# i2cLCD.net
KiCad netlist of a schematic drawn in EAGLE
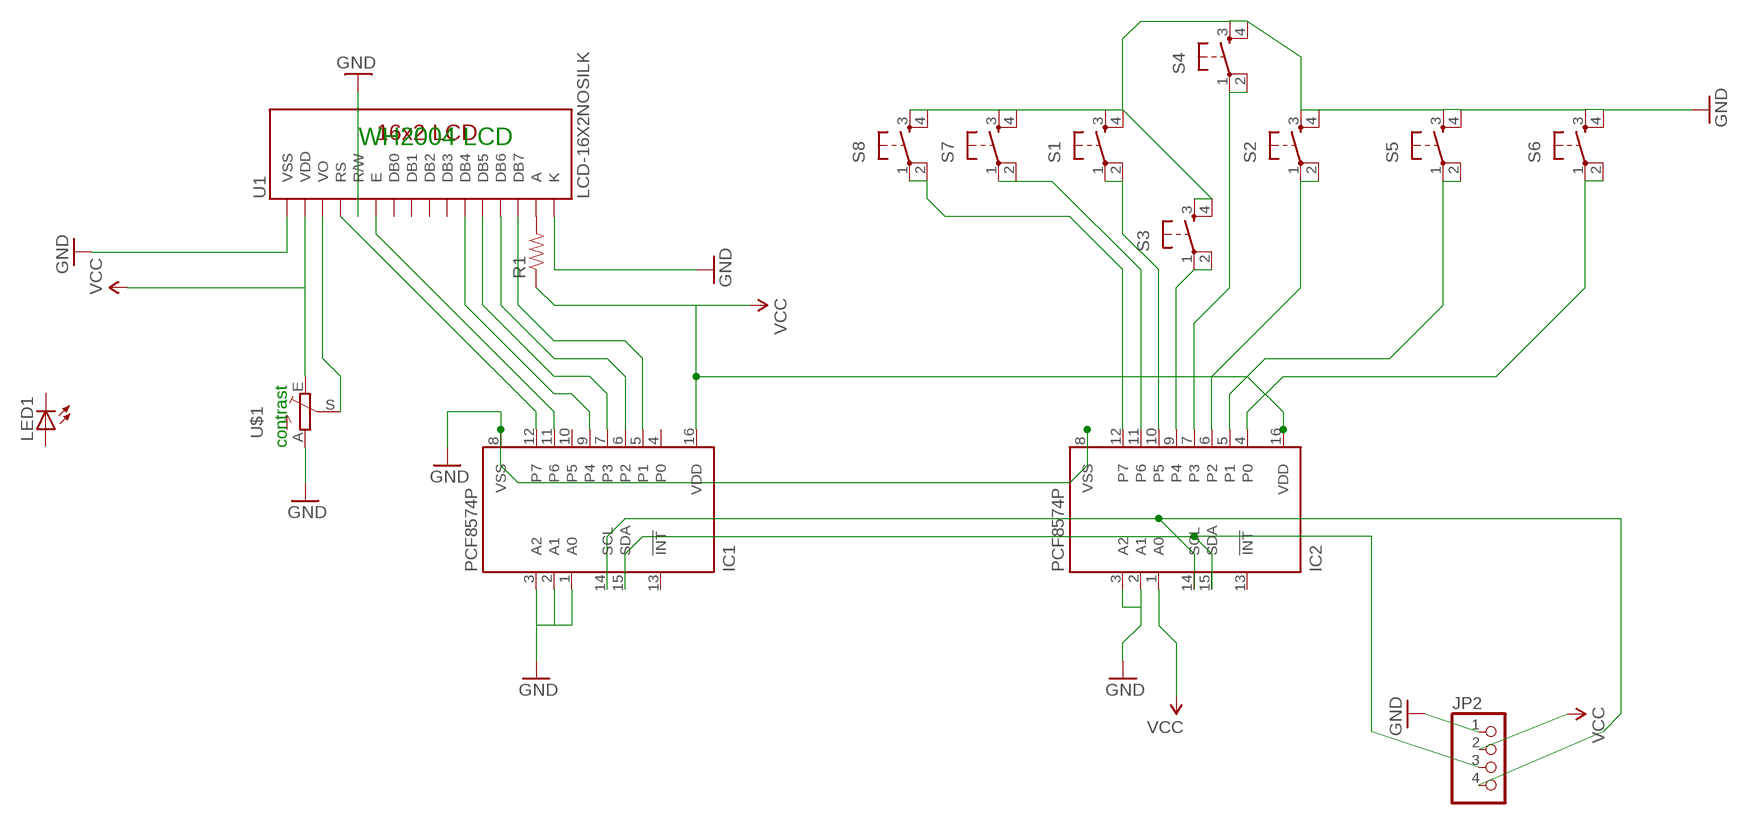
[diagram p0: schematic, sheet 1]

(export (version "E")
  (design (tool "Eeschema 10.0.6"))
  (components
    (comp (ref "IC1")
      (value "PCF8574P")
      (footprint "eagle-import:DIL16")
      (fields (field (name "MPN") "PCF8574PN"))
      (libsource (lib "eagle-import") (part "PCF8574P"))
    )
    (comp (ref "IC2")
      (value "PCF8574P")
      (footprint "eagle-import:DIL16")
      (fields
        (field (name "MPN") "PCF8574PN")
        (field (name "MPN_1") "PCF8574PN")
        (field (name "OC_FARNELL") "204020")
        (field (name "OC_NEWARK") "11N8515")
      )
      (libsource (lib "eagle-import") (part "PCF8574P"))
    )
    (comp (ref "JP2")
      (value "PINHD-1X4/90")
      (footprint "eagle-import:1X04_90")
      (libsource (lib "eagle-import") (part "PINHD-1X4/90"))
    )
    (comp (ref "LED1")
      (value "LED1206")
      (footprint "eagle-import:LED-1206")
      (libsource (lib "eagle-import") (part "LED1206"))
    )
    (comp (ref "R1")
      (value "RESISTORPTH-1/4W")
      (footprint "eagle-import:AXIAL-0.4")
      (libsource (lib "eagle-import") (part "RESISTORPTH-1/4W"))
    )
    (comp (ref "S1")
      (value "TAC_SWITCHPTH")
      (footprint "eagle-import:TACTILE-PTH")
      (libsource (lib "eagle-import") (part "TAC_SWITCHPTH"))
    )
    (comp (ref "S2")
      (value "TAC_SWITCHPTH")
      (footprint "eagle-import:TACTILE-PTH")
      (libsource (lib "eagle-import") (part "TAC_SWITCHPTH"))
    )
    (comp (ref "S3")
      (value "TAC_SWITCHPTH")
      (footprint "eagle-import:TACTILE-PTH")
      (libsource (lib "eagle-import") (part "TAC_SWITCHPTH"))
    )
    (comp (ref "S4")
      (value "TAC_SWITCHPTH")
      (footprint "eagle-import:TACTILE-PTH")
      (libsource (lib "eagle-import") (part "TAC_SWITCHPTH"))
    )
    (comp (ref "S5")
      (value "TAC_SWITCHPTH")
      (footprint "eagle-import:TACTILE-PTH")
      (libsource (lib "eagle-import") (part "TAC_SWITCHPTH"))
    )
    (comp (ref "S6")
      (value "TAC_SWITCHPTH")
      (footprint "eagle-import:TACTILE-PTH")
      (libsource (lib "eagle-import") (part "TAC_SWITCHPTH"))
    )
    (comp (ref "S7")
      (value "TAC_SWITCHPTH")
      (footprint "eagle-import:TACTILE-PTH")
      (libsource (lib "eagle-import") (part "TAC_SWITCHPTH"))
    )
    (comp (ref "S8")
      (value "TAC_SWITCHPTH")
      (footprint "eagle-import:TACTILE-PTH")
      (libsource (lib "eagle-import") (part "TAC_SWITCHPTH"))
    )
    (comp (ref "U$1")
      (value "TRIM_EU-CA9V")
      (footprint "eagle-import:CA9V")
      (libsource (lib "eagle-import") (part "TRIM_EU-CA9V"))
    )
    (comp (ref "U1")
      (value "LCD-16X2NOSILK")
      (footprint "eagle-import:LCD-16X2_NOSILK")
      (libsource (lib "eagle-import") (part "LCD-16X2NOSILK"))
    )
  )
  (nets
    (net (code "1") (name "GND") (class "Default")
      (node (ref "IC1") (pin "1") (pinfunction "A0_1") (pintype "input"))
      (node (ref "IC1") (pin "2") (pinfunction "A1_2") (pintype "input"))
      (node (ref "IC1") (pin "3") (pinfunction "A2_3") (pintype "input"))
      (node (ref "IC1") (pin "8") (pinfunction "VSS_8") (pintype "power_in"))
      (node (ref "IC2") (pin "2") (pinfunction "A1_2") (pintype "input"))
      (node (ref "IC2") (pin "3") (pinfunction "A2_3") (pintype "input"))
      (node (ref "IC2") (pin "8") (pinfunction "VSS_8") (pintype "power_in"))
      (node (ref "JP2") (pin "1") (pinfunction "1_1") (pintype "passive"))
      (node (ref "S1") (pin "3") (pinfunction "3_3") (pintype "passive"))
      (node (ref "S1") (pin "4") (pinfunction "4_4") (pintype "passive"))
      (node (ref "S2") (pin "3") (pinfunction "3_3") (pintype "passive"))
      (node (ref "S2") (pin "4") (pinfunction "4_4") (pintype "passive"))
      (node (ref "S3") (pin "3") (pinfunction "3_3") (pintype "passive"))
      (node (ref "S3") (pin "4") (pinfunction "4_4") (pintype "passive"))
      (node (ref "S4") (pin "3") (pinfunction "3_3") (pintype "passive"))
      (node (ref "S4") (pin "4") (pinfunction "4_4") (pintype "passive"))
      (node (ref "S5") (pin "3") (pinfunction "3_3") (pintype "passive"))
      (node (ref "S5") (pin "4") (pinfunction "4_4") (pintype "passive"))
      (node (ref "S6") (pin "3") (pinfunction "3_3") (pintype "passive"))
      (node (ref "S6") (pin "4") (pinfunction "4_4") (pintype "passive"))
      (node (ref "S7") (pin "3") (pinfunction "3_3") (pintype "passive"))
      (node (ref "S7") (pin "4") (pinfunction "4_4") (pintype "passive"))
      (node (ref "S8") (pin "3") (pinfunction "3_3") (pintype "passive"))
      (node (ref "S8") (pin "4") (pinfunction "4_4") (pintype "passive"))
      (node (ref "U$1") (pin "A") (pinfunction "A_A") (pintype "passive"))
      (node (ref "U1") (pin "1") (pinfunction "VSS_1") (pintype "power_in"))
      (node (ref "U1") (pin "16") (pinfunction "K_16") (pintype "power_in"))
      (node (ref "U1") (pin "5") (pinfunction "R/W_5") (pintype "input"))
    )
    (net (code "2") (name "Net-(IC1-P1)") (class "Default")
      (node (ref "IC1") (pin "5") (pinfunction "P1_5") (pintype "bidirectional"))
      (node (ref "U1") (pin "14") (pinfunction "DB7_14") (pintype "bidirectional"))
    )
    (net (code "3") (name "Net-(IC1-P2)") (class "Default")
      (node (ref "IC1") (pin "6") (pinfunction "P2_6") (pintype "bidirectional"))
      (node (ref "U1") (pin "13") (pinfunction "DB6_13") (pintype "bidirectional"))
    )
    (net (code "4") (name "Net-(IC1-P3)") (class "Default")
      (node (ref "IC1") (pin "7") (pinfunction "P3_7") (pintype "bidirectional"))
      (node (ref "U1") (pin "12") (pinfunction "DB5_12") (pintype "bidirectional"))
    )
    (net (code "5") (name "Net-(IC1-P4)") (class "Default")
      (node (ref "IC1") (pin "9") (pinfunction "P4_9") (pintype "bidirectional"))
      (node (ref "U1") (pin "11") (pinfunction "DB4_11") (pintype "bidirectional"))
    )
    (net (code "6") (name "Net-(IC1-P6)") (class "Default")
      (node (ref "IC1") (pin "11") (pinfunction "P6_11") (pintype "bidirectional"))
      (node (ref "U1") (pin "6") (pinfunction "E_6") (pintype "input"))
    )
    (net (code "7") (name "Net-(IC1-P7)") (class "Default")
      (node (ref "IC1") (pin "12") (pinfunction "P7_12") (pintype "bidirectional"))
      (node (ref "U1") (pin "4") (pinfunction "RS_4") (pintype "input"))
    )
    (net (code "8") (name "Net-(IC1-SCL)") (class "Default")
      (node (ref "IC1") (pin "14") (pinfunction "SCL_14") (pintype "input"))
      (node (ref "IC2") (pin "14") (pinfunction "SCL_14") (pintype "input"))
      (node (ref "JP2") (pin "4") (pinfunction "4_4") (pintype "passive"))
    )
    (net (code "9") (name "Net-(IC1-SDA)") (class "Default")
      (node (ref "IC1") (pin "15") (pinfunction "SDA_15") (pintype "bidirectional"))
      (node (ref "IC2") (pin "15") (pinfunction "SDA_15") (pintype "bidirectional"))
      (node (ref "JP2") (pin "3") (pinfunction "3_3") (pintype "passive"))
    )
    (net (code "10") (name "Net-(IC2-P0)") (class "Default")
      (node (ref "IC2") (pin "4") (pinfunction "P0_4") (pintype "bidirectional"))
      (node (ref "S6") (pin "1") (pinfunction "1_1") (pintype "passive"))
      (node (ref "S6") (pin "2") (pinfunction "2_2") (pintype "passive"))
    )
    (net (code "11") (name "Net-(IC2-P1)") (class "Default")
      (node (ref "IC2") (pin "5") (pinfunction "P1_5") (pintype "bidirectional"))
      (node (ref "S5") (pin "1") (pinfunction "1_1") (pintype "passive"))
      (node (ref "S5") (pin "2") (pinfunction "2_2") (pintype "passive"))
    )
    (net (code "12") (name "Net-(IC2-P2)") (class "Default")
      (node (ref "IC2") (pin "6") (pinfunction "P2_6") (pintype "bidirectional"))
      (node (ref "S2") (pin "1") (pinfunction "1_1") (pintype "passive"))
      (node (ref "S2") (pin "2") (pinfunction "2_2") (pintype "passive"))
    )
    (net (code "13") (name "Net-(IC2-P3)") (class "Default")
      (node (ref "IC2") (pin "7") (pinfunction "P3_7") (pintype "bidirectional"))
      (node (ref "S4") (pin "1") (pinfunction "1_1") (pintype "passive"))
      (node (ref "S4") (pin "2") (pinfunction "2_2") (pintype "passive"))
    )
    (net (code "14") (name "Net-(IC2-P4)") (class "Default")
      (node (ref "IC2") (pin "9") (pinfunction "P4_9") (pintype "bidirectional"))
      (node (ref "S3") (pin "1") (pinfunction "1_1") (pintype "passive"))
      (node (ref "S3") (pin "2") (pinfunction "2_2") (pintype "passive"))
    )
    (net (code "15") (name "Net-(IC2-P5)") (class "Default")
      (node (ref "IC2") (pin "10") (pinfunction "P5_10") (pintype "bidirectional"))
      (node (ref "S1") (pin "1") (pinfunction "1_1") (pintype "passive"))
      (node (ref "S1") (pin "2") (pinfunction "2_2") (pintype "passive"))
    )
    (net (code "16") (name "Net-(IC2-P6)") (class "Default")
      (node (ref "IC2") (pin "11") (pinfunction "P6_11") (pintype "bidirectional"))
      (node (ref "S7") (pin "1") (pinfunction "1_1") (pintype "passive"))
      (node (ref "S7") (pin "2") (pinfunction "2_2") (pintype "passive"))
    )
    (net (code "17") (name "Net-(IC2-P7)") (class "Default")
      (node (ref "IC2") (pin "12") (pinfunction "P7_12") (pintype "bidirectional"))
      (node (ref "S8") (pin "1") (pinfunction "1_1") (pintype "passive"))
      (node (ref "S8") (pin "2") (pinfunction "2_2") (pintype "passive"))
    )
    (net (code "18") (name "Net-(R1-2)") (class "Default")
      (node (ref "R1") (pin "P$2") (pinfunction "2_P$2") (pintype "passive"))
      (node (ref "U1") (pin "15") (pinfunction "A_15") (pintype "power_in"))
    )
    (net (code "19") (name "Net-(U1-VO)") (class "Default")
      (node (ref "U$1") (pin "S") (pinfunction "S_S") (pintype "passive"))
      (node (ref "U1") (pin "3") (pinfunction "VO_3") (pintype "bidirectional"))
    )
    (net (code "20") (name "VCC") (class "Default")
      (node (ref "IC1") (pin "16") (pinfunction "VDD_16") (pintype "power_in"))
      (node (ref "IC2") (pin "1") (pinfunction "A0_1") (pintype "input"))
      (node (ref "IC2") (pin "16") (pinfunction "VDD_16") (pintype "power_in"))
      (node (ref "JP2") (pin "2") (pinfunction "2_2") (pintype "passive"))
      (node (ref "R1") (pin "P$1") (pinfunction "1_P$1") (pintype "passive"))
      (node (ref "U$1") (pin "E") (pinfunction "E_E") (pintype "passive"))
      (node (ref "U1") (pin "2") (pinfunction "VDD_2") (pintype "power_in"))
    )
    (net (code "21") (name "unconnected-(IC1-P0-Pad4)") (class "Default")
      (node (ref "IC1") (pin "4") (pinfunction "P0_4") (pintype "bidirectional"))
    )
    (net (code "22") (name "unconnected-(IC1-P5-Pad10)") (class "Default")
      (node (ref "IC1") (pin "10") (pinfunction "P5_10") (pintype "bidirectional"))
    )
    (net (code "23") (name "unconnected-(IC1-~{INT}-Pad13)") (class "Default")
      (node (ref "IC1") (pin "13") (pinfunction "~{INT}_13") (pintype "output"))
    )
    (net (code "24") (name "unconnected-(IC2-~{INT}-Pad13)") (class "Default")
      (node (ref "IC2") (pin "13") (pinfunction "~{INT}_13") (pintype "output"))
    )
    (net (code "25") (name "unconnected-(LED1-PadA)") (class "Default")
      (node (ref "LED1") (pin "A") (pinfunction "A_A") (pintype "passive"))
    )
    (net (code "26") (name "unconnected-(LED1-PadC)") (class "Default")
      (node (ref "LED1") (pin "C") (pinfunction "C_C") (pintype "passive"))
    )
    (net (code "27") (name "unconnected-(U1-DB0-Pad7)") (class "Default")
      (node (ref "U1") (pin "7") (pinfunction "DB0_7") (pintype "bidirectional"))
    )
    (net (code "28") (name "unconnected-(U1-DB1-Pad8)") (class "Default")
      (node (ref "U1") (pin "8") (pinfunction "DB1_8") (pintype "bidirectional"))
    )
    (net (code "29") (name "unconnected-(U1-DB2-Pad9)") (class "Default")
      (node (ref "U1") (pin "9") (pinfunction "DB2_9") (pintype "bidirectional"))
    )
    (net (code "30") (name "unconnected-(U1-DB3-Pad10)") (class "Default")
      (node (ref "U1") (pin "10") (pinfunction "DB3_10") (pintype "bidirectional"))
    )
  )
)
